# OpAmpCircuit.net
KiCad netlist of a schematic drawn in Altium Designer
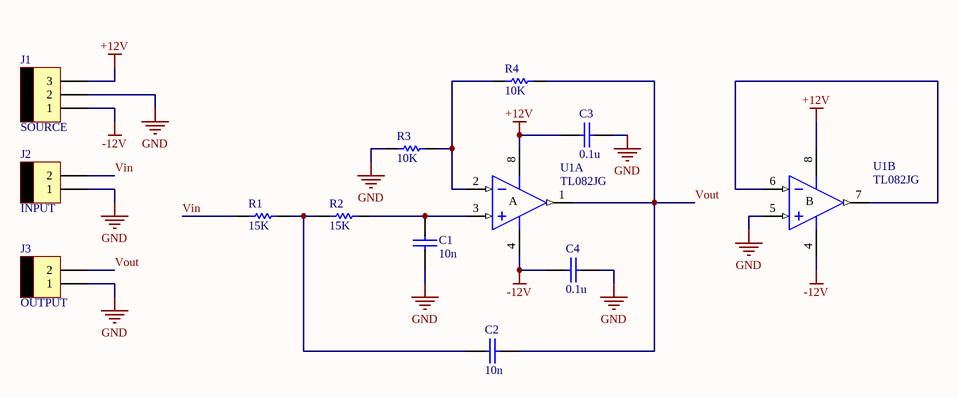
[diagram p0: OpAmpCircuit.SchDoc]

(export (version "E")
  (design (tool "Eeschema 10.0.6"))
  (components
    (comp (ref "C1") (value "10n") (footprint "CAP200") (libsource (lib "LIBEBAL") (part "CAP")))
    (comp (ref "C2") (value "10n") (footprint "CAP200") (libsource (lib "LIBEBAL") (part "CAP")))
    (comp (ref "C3") (value "0.1u") (footprint "CAP200") (libsource (lib "LIBEBAL") (part "CAP")))
    (comp (ref "C4") (value "0.1u") (footprint "CAP200") (libsource (lib "LIBEBAL") (part "CAP")))
    (comp (ref "J1") (value "SOURCE") (footprint "MOLEX3") (libsource (lib "LIBEBAL") (part "MOLEX3")))
    (comp (ref "J2") (value "INPUT") (footprint "MOLEX2") (libsource (lib "LIBEBAL") (part "MOLEX2")))
    (comp (ref "J3") (value "OUTPUT") (footprint "MOLEX2") (libsource (lib "LIBEBAL") (part "MOLEX2")))
    (comp (ref "R1") (value "15K") (footprint "RES400") (libsource (lib "LIBEBAL") (part "RES")))
    (comp (ref "R2") (value "15K") (footprint "RES400") (libsource (lib "LIBEBAL") (part "RES")))
    (comp (ref "R3") (value "10K") (footprint "RES400") (libsource (lib "LIBEBAL") (part "RES")))
    (comp (ref "R4") (value "10K") (footprint "RES400") (libsource (lib "LIBEBAL") (part "RES")))
    (comp (ref "U1")
      (value "TL082JG")
      (footprint "JG008")
      (description "JFET-Input Operational Amplifier")
      (fields (field (name "PUBLISHER") "Altium Limited"))
      (libsource (lib "TI Operational Amplifier") (part "TL082JG"))
    )
  )
  (nets
    (net (code "1") (name "+12V") (class "Default")
      (node (ref "C3") (pin "1") (pinfunction "1_1") (pintype "passive"))
      (node (ref "J1") (pin "3") (pinfunction "3_3") (pintype "passive"))
      (node (ref "U1") (pin "8") (pinfunction "V+_8") (pintype "power_in"))
    )
    (net (code "2") (name "-12V") (class "Default")
      (node (ref "C4") (pin "1") (pinfunction "1_1") (pintype "passive"))
      (node (ref "J1") (pin "1") (pinfunction "1_1") (pintype "passive"))
      (node (ref "U1") (pin "4") (pinfunction "V-_4") (pintype "power_in"))
    )
    (net (code "3") (name "/Vin") (class "Default")
      (node (ref "J2") (pin "2") (pinfunction "2_2") (pintype "passive"))
      (node (ref "R1") (pin "1") (pinfunction "1_1") (pintype "passive"))
    )
    (net (code "4") (name "/Vout") (class "Default")
      (node (ref "C2") (pin "1") (pinfunction "1_1") (pintype "passive"))
      (node (ref "J3") (pin "2") (pinfunction "2_2") (pintype "passive"))
      (node (ref "R4") (pin "2") (pinfunction "2_2") (pintype "passive"))
      (node (ref "U1") (pin "1") (pinfunction "OUT_1") (pintype "output"))
    )
    (net (code "5") (name "GND") (class "Default")
      (node (ref "C1") (pin "2") (pinfunction "2_2") (pintype "passive"))
      (node (ref "C3") (pin "2") (pinfunction "2_2") (pintype "passive"))
      (node (ref "C4") (pin "2") (pinfunction "2_2") (pintype "passive"))
      (node (ref "J1") (pin "2") (pinfunction "2_2") (pintype "passive"))
      (node (ref "J2") (pin "1") (pinfunction "1_1") (pintype "passive"))
      (node (ref "J3") (pin "1") (pinfunction "1_1") (pintype "passive"))
      (node (ref "R3") (pin "1") (pinfunction "1_1") (pintype "passive"))
      (node (ref "U1") (pin "5") (pinfunction "IN+_5") (pintype "input"))
    )
    (net (code "6") (name "Net-(C2-Pad2)") (class "Default")
      (node (ref "C2") (pin "2") (pinfunction "2_2") (pintype "passive"))
      (node (ref "R1") (pin "2") (pinfunction "2_2") (pintype "passive"))
      (node (ref "R2") (pin "1") (pinfunction "1_1") (pintype "passive"))
    )
    (net (code "7") (name "Net-(U1A-IN+)") (class "Default")
      (node (ref "C1") (pin "1") (pinfunction "1_1") (pintype "passive"))
      (node (ref "R2") (pin "2") (pinfunction "2_2") (pintype "passive"))
      (node (ref "U1") (pin "3") (pinfunction "IN+_3") (pintype "input"))
    )
    (net (code "8") (name "Net-(U1A-IN-)") (class "Default")
      (node (ref "R3") (pin "2") (pinfunction "2_2") (pintype "passive"))
      (node (ref "R4") (pin "1") (pinfunction "1_1") (pintype "passive"))
      (node (ref "U1") (pin "2") (pinfunction "IN-_2") (pintype "input"))
    )
    (net (code "9") (name "Net-(U1B-IN-)") (class "Default")
      (node (ref "U1") (pin "6") (pinfunction "IN-_6") (pintype "input"))
      (node (ref "U1") (pin "7") (pinfunction "OUT_7") (pintype "output"))
    )
  )
)
